# SRAM.net
KiCad netlist of a schematic drawn in Altium Designer
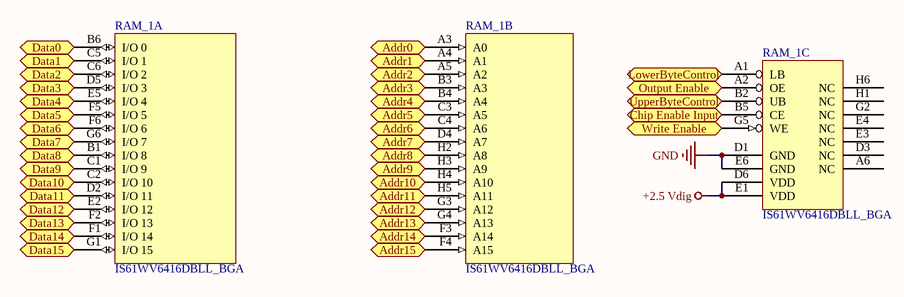
[diagram p0: SRAM.SchDoc]

(export (version "E")
  (design (tool "Eeschema 10.0.6"))
  (components
    (comp (ref "RAM_1")
      (value "IS61WV6416DBLL_BGA")
      (footprint "TF-BGA 48L 6x8mm")
      (libsource (lib "vMemory") (part "IS61WV6416DBLL_BGA"))
    )
  )
  (nets
    (net (code "1") (name "+2.5 Vdig") (class "Default")
      (node (ref "RAM_1") (pin "D6") (pinfunction "VDD_D6") (pintype "power_in"))
      (node (ref "RAM_1") (pin "E1") (pinfunction "VDD_E1") (pintype "power_in"))
    )
    (net (code "2") (name "/Addr0") (class "Default")
      (node (ref "RAM_1") (pin "A3") (pinfunction "A0_A3") (pintype "input"))
    )
    (net (code "3") (name "/Addr1") (class "Default")
      (node (ref "RAM_1") (pin "A4") (pinfunction "A1_A4") (pintype "input"))
    )
    (net (code "4") (name "/Addr2") (class "Default")
      (node (ref "RAM_1") (pin "A5") (pinfunction "A2_A5") (pintype "input"))
    )
    (net (code "5") (name "/Addr3") (class "Default")
      (node (ref "RAM_1") (pin "B3") (pinfunction "A3_B3") (pintype "input"))
    )
    (net (code "6") (name "/Addr4") (class "Default")
      (node (ref "RAM_1") (pin "B4") (pinfunction "A4_B4") (pintype "input"))
    )
    (net (code "7") (name "/Addr5") (class "Default")
      (node (ref "RAM_1") (pin "C3") (pinfunction "A5_C3") (pintype "input"))
    )
    (net (code "8") (name "/Addr6") (class "Default")
      (node (ref "RAM_1") (pin "C4") (pinfunction "A6_C4") (pintype "input"))
    )
    (net (code "9") (name "/Addr7") (class "Default")
      (node (ref "RAM_1") (pin "D4") (pinfunction "A7_D4") (pintype "input"))
    )
    (net (code "10") (name "/Addr8") (class "Default")
      (node (ref "RAM_1") (pin "H2") (pinfunction "A8_H2") (pintype "input"))
    )
    (net (code "11") (name "/Addr9") (class "Default")
      (node (ref "RAM_1") (pin "H3") (pinfunction "A9_H3") (pintype "input"))
    )
    (net (code "12") (name "/Addr10") (class "Default")
      (node (ref "RAM_1") (pin "H4") (pinfunction "A10_H4") (pintype "input"))
    )
    (net (code "13") (name "/Addr11") (class "Default")
      (node (ref "RAM_1") (pin "H5") (pinfunction "A11_H5") (pintype "input"))
    )
    (net (code "14") (name "/Addr12") (class "Default")
      (node (ref "RAM_1") (pin "G3") (pinfunction "A12_G3") (pintype "input"))
    )
    (net (code "15") (name "/Addr13") (class "Default")
      (node (ref "RAM_1") (pin "G4") (pinfunction "A13_G4") (pintype "input"))
    )
    (net (code "16") (name "/Addr14") (class "Default")
      (node (ref "RAM_1") (pin "F3") (pinfunction "A14_F3") (pintype "input"))
    )
    (net (code "17") (name "/Addr15") (class "Default")
      (node (ref "RAM_1") (pin "F4") (pinfunction "A15_F4") (pintype "input"))
    )
    (net (code "18") (name "/Chip Enable Input") (class "Default")
      (node (ref "RAM_1") (pin "B5") (pinfunction "CE_B5") (pintype "passive"))
    )
    (net (code "19") (name "/Data0") (class "Default")
      (node (ref "RAM_1") (pin "B6") (pinfunction "I/O_0_B6") (pintype "bidirectional"))
    )
    (net (code "20") (name "/Data1") (class "Default")
      (node (ref "RAM_1") (pin "C5") (pinfunction "I/O_1_C5") (pintype "bidirectional"))
    )
    (net (code "21") (name "/Data2") (class "Default")
      (node (ref "RAM_1") (pin "C6") (pinfunction "I/O_2_C6") (pintype "bidirectional"))
    )
    (net (code "22") (name "/Data3") (class "Default")
      (node (ref "RAM_1") (pin "D5") (pinfunction "I/O_3_D5") (pintype "bidirectional"))
    )
    (net (code "23") (name "/Data4") (class "Default")
      (node (ref "RAM_1") (pin "E5") (pinfunction "I/O_4_E5") (pintype "bidirectional"))
    )
    (net (code "24") (name "/Data5") (class "Default")
      (node (ref "RAM_1") (pin "F5") (pinfunction "I/O_5_F5") (pintype "bidirectional"))
    )
    (net (code "25") (name "/Data6") (class "Default")
      (node (ref "RAM_1") (pin "F6") (pinfunction "I/O_6_F6") (pintype "bidirectional"))
    )
    (net (code "26") (name "/Data7") (class "Default")
      (node (ref "RAM_1") (pin "G6") (pinfunction "I/O_7_G6") (pintype "bidirectional"))
    )
    (net (code "27") (name "/Data8") (class "Default")
      (node (ref "RAM_1") (pin "B1") (pinfunction "I/O_8_B1") (pintype "bidirectional"))
    )
    (net (code "28") (name "/Data9") (class "Default")
      (node (ref "RAM_1") (pin "C1") (pinfunction "I/O_9_C1") (pintype "bidirectional"))
    )
    (net (code "29") (name "/Data10") (class "Default")
      (node (ref "RAM_1") (pin "C2") (pinfunction "I/O_10_C2") (pintype "bidirectional"))
    )
    (net (code "30") (name "/Data11") (class "Default")
      (node (ref "RAM_1") (pin "D2") (pinfunction "I/O_11_D2") (pintype "bidirectional"))
    )
    (net (code "31") (name "/Data12") (class "Default")
      (node (ref "RAM_1") (pin "E2") (pinfunction "I/O_12_E2") (pintype "bidirectional"))
    )
    (net (code "32") (name "/Data13") (class "Default")
      (node (ref "RAM_1") (pin "F2") (pinfunction "I/O_13_F2") (pintype "bidirectional"))
    )
    (net (code "33") (name "/Data14") (class "Default")
      (node (ref "RAM_1") (pin "F1") (pinfunction "I/O_14_F1") (pintype "bidirectional"))
    )
    (net (code "34") (name "/Data15") (class "Default")
      (node (ref "RAM_1") (pin "G1") (pinfunction "I/O_15_G1") (pintype "bidirectional"))
    )
    (net (code "35") (name "/LowerByteControl") (class "Default")
      (node (ref "RAM_1") (pin "A1") (pinfunction "LB_A1") (pintype "passive"))
    )
    (net (code "36") (name "/Output Enable") (class "Default")
      (node (ref "RAM_1") (pin "A2") (pinfunction "OE_A2") (pintype "passive"))
    )
    (net (code "37") (name "/UpperByteControl") (class "Default")
      (node (ref "RAM_1") (pin "B2") (pinfunction "UB_B2") (pintype "passive"))
    )
    (net (code "38") (name "/Write Enable") (class "Default")
      (node (ref "RAM_1") (pin "G5") (pinfunction "WE_G5") (pintype "input"))
    )
    (net (code "39") (name "GND") (class "Default")
      (node (ref "RAM_1") (pin "D1") (pinfunction "GND_D1") (pintype "power_in"))
      (node (ref "RAM_1") (pin "E6") (pinfunction "GND_E6") (pintype "power_in"))
    )
    (net (code "40") (name "unconnected-(RAM_1C-NC-PadA6)") (class "Default")
      (node (ref "RAM_1") (pin "A6") (pinfunction "NC_A6") (pintype "passive"))
    )
    (net (code "41") (name "unconnected-(RAM_1C-NC-PadD3)") (class "Default")
      (node (ref "RAM_1") (pin "D3") (pinfunction "NC_D3") (pintype "passive"))
    )
    (net (code "42") (name "unconnected-(RAM_1C-NC-PadE3)") (class "Default")
      (node (ref "RAM_1") (pin "E3") (pinfunction "NC_E3") (pintype "passive"))
    )
    (net (code "43") (name "unconnected-(RAM_1C-NC-PadE4)") (class "Default")
      (node (ref "RAM_1") (pin "E4") (pinfunction "NC_E4") (pintype "passive"))
    )
    (net (code "44") (name "unconnected-(RAM_1C-NC-PadG2)") (class "Default")
      (node (ref "RAM_1") (pin "G2") (pinfunction "NC_G2") (pintype "power_in"))
    )
    (net (code "45") (name "unconnected-(RAM_1C-NC-PadH1)") (class "Default")
      (node (ref "RAM_1") (pin "H1") (pinfunction "NC_H1") (pintype "passive"))
    )
    (net (code "46") (name "unconnected-(RAM_1C-NC-PadH6)") (class "Default")
      (node (ref "RAM_1") (pin "H6") (pinfunction "NC_H6") (pintype "passive"))
    )
  )
)
